# hydrogen_sensors_board_v4_0.net
KiCad netlist of a schematic drawn in EAGLE
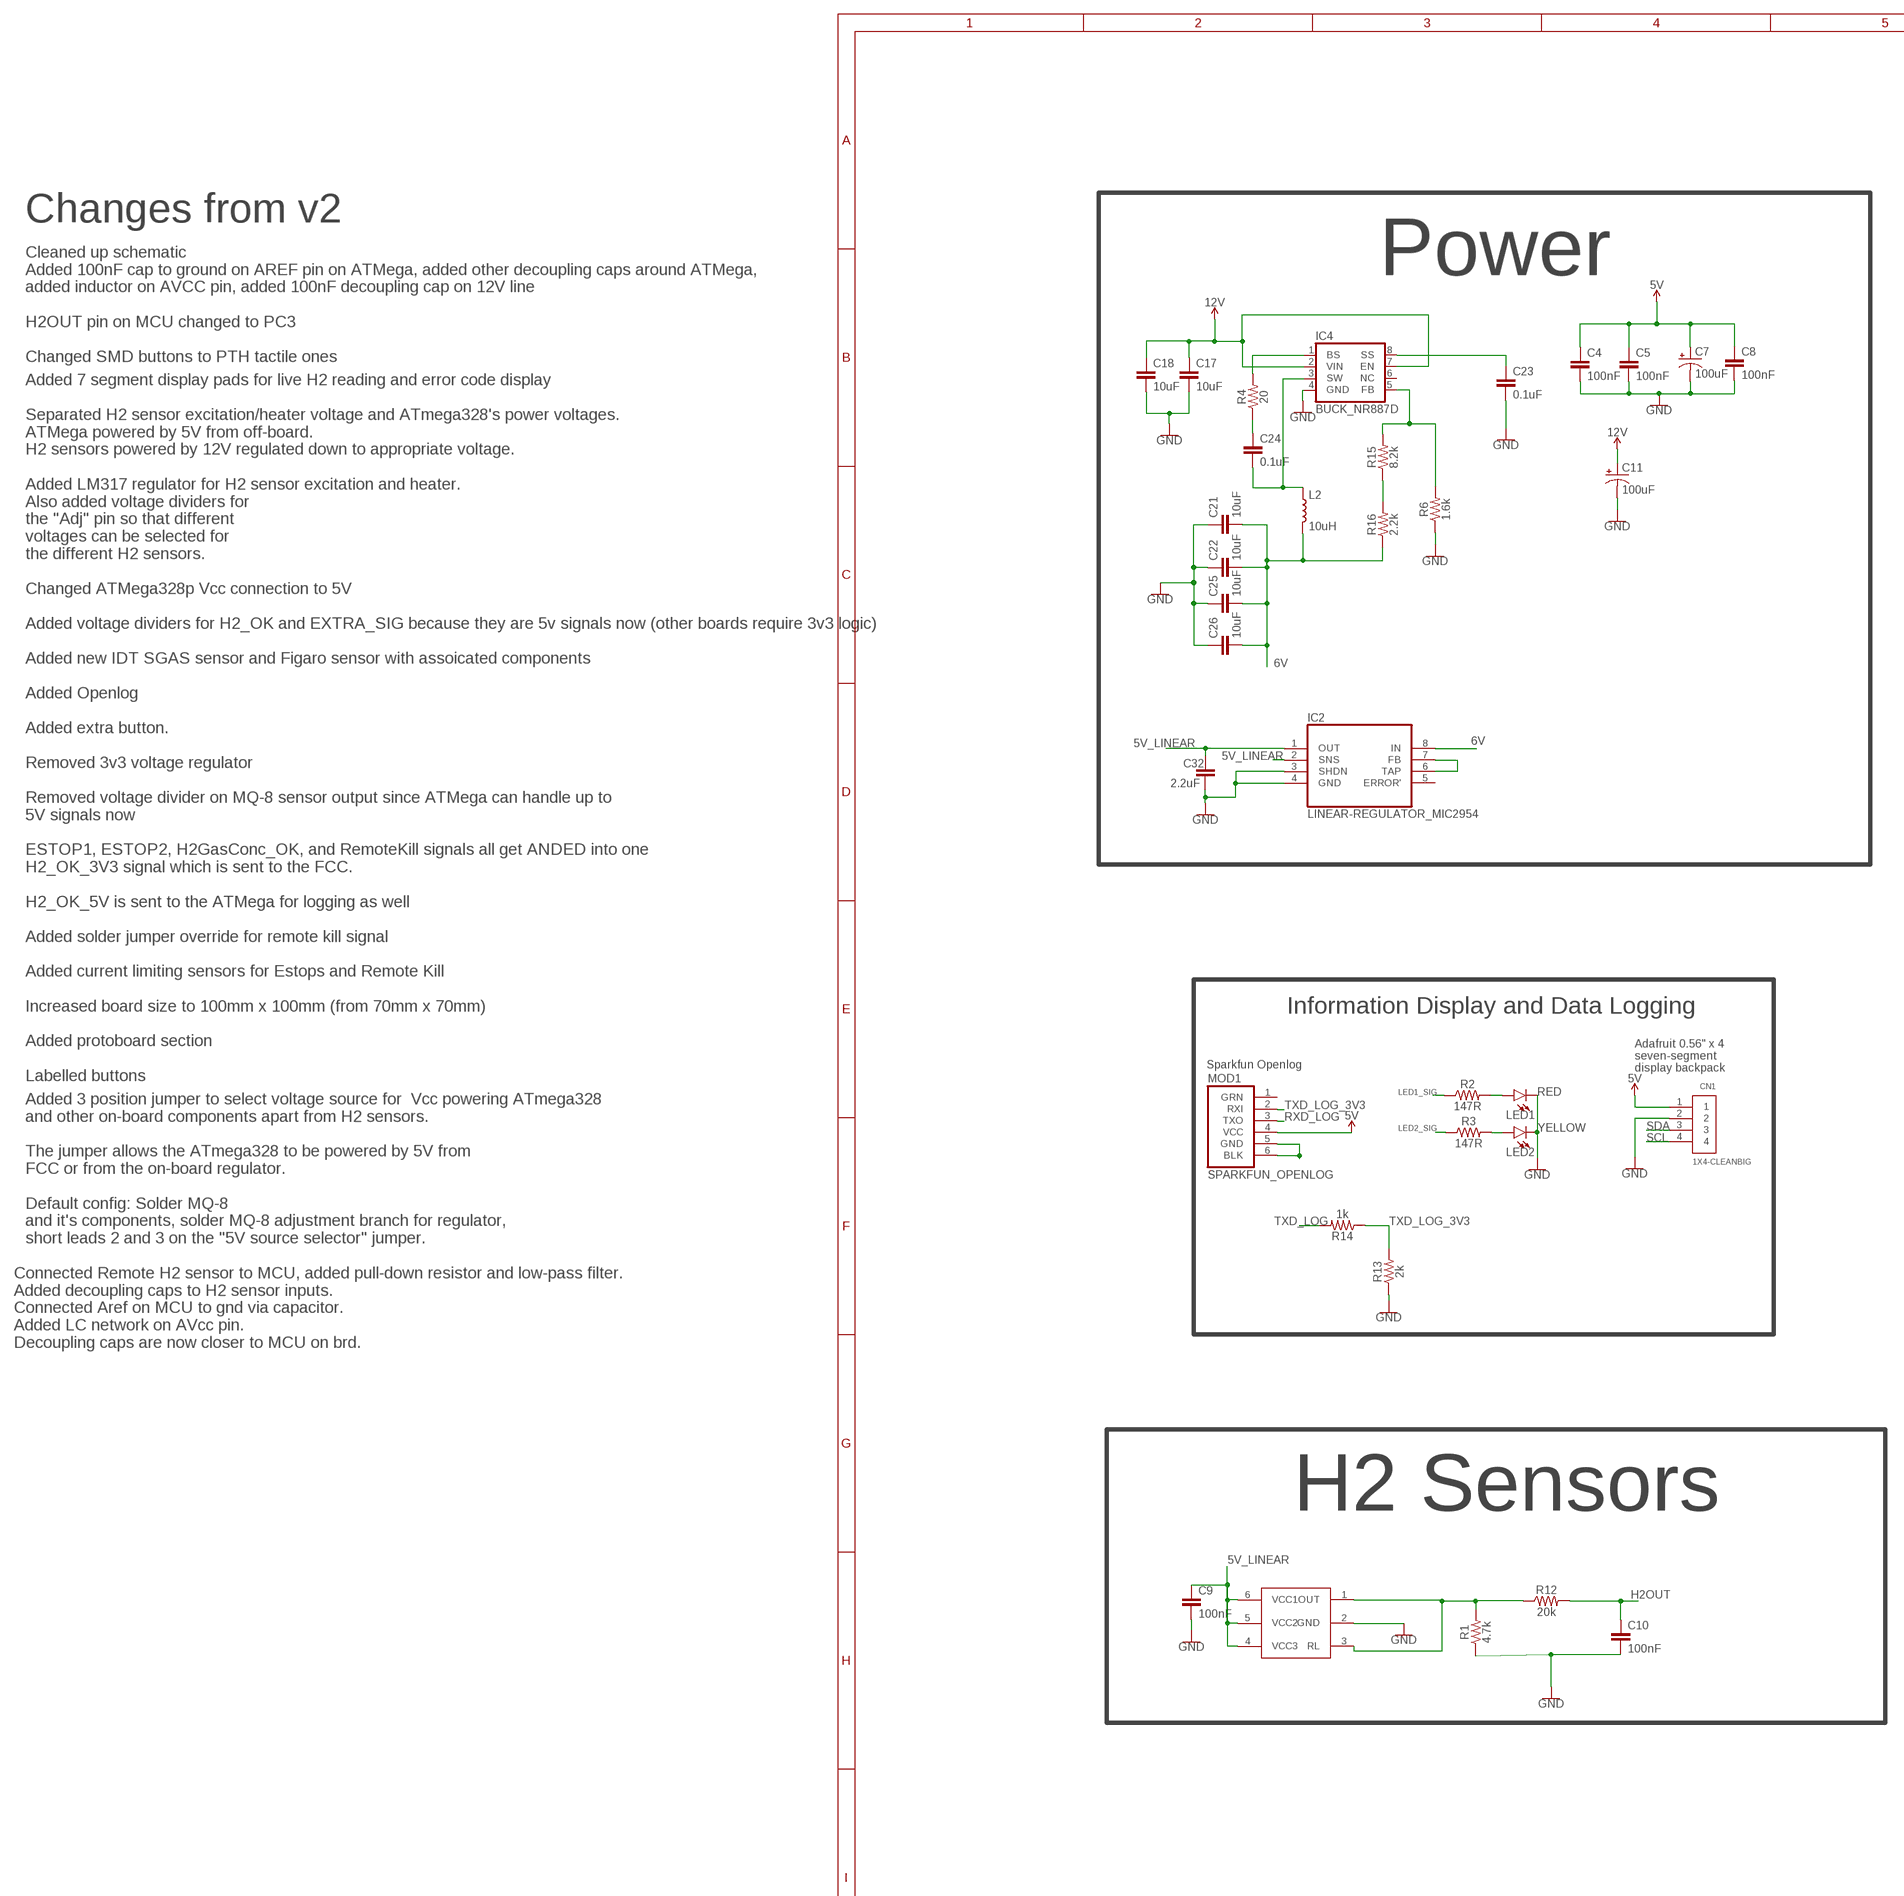
[diagram p0: schematic, sheet 1, part 1 of 2]
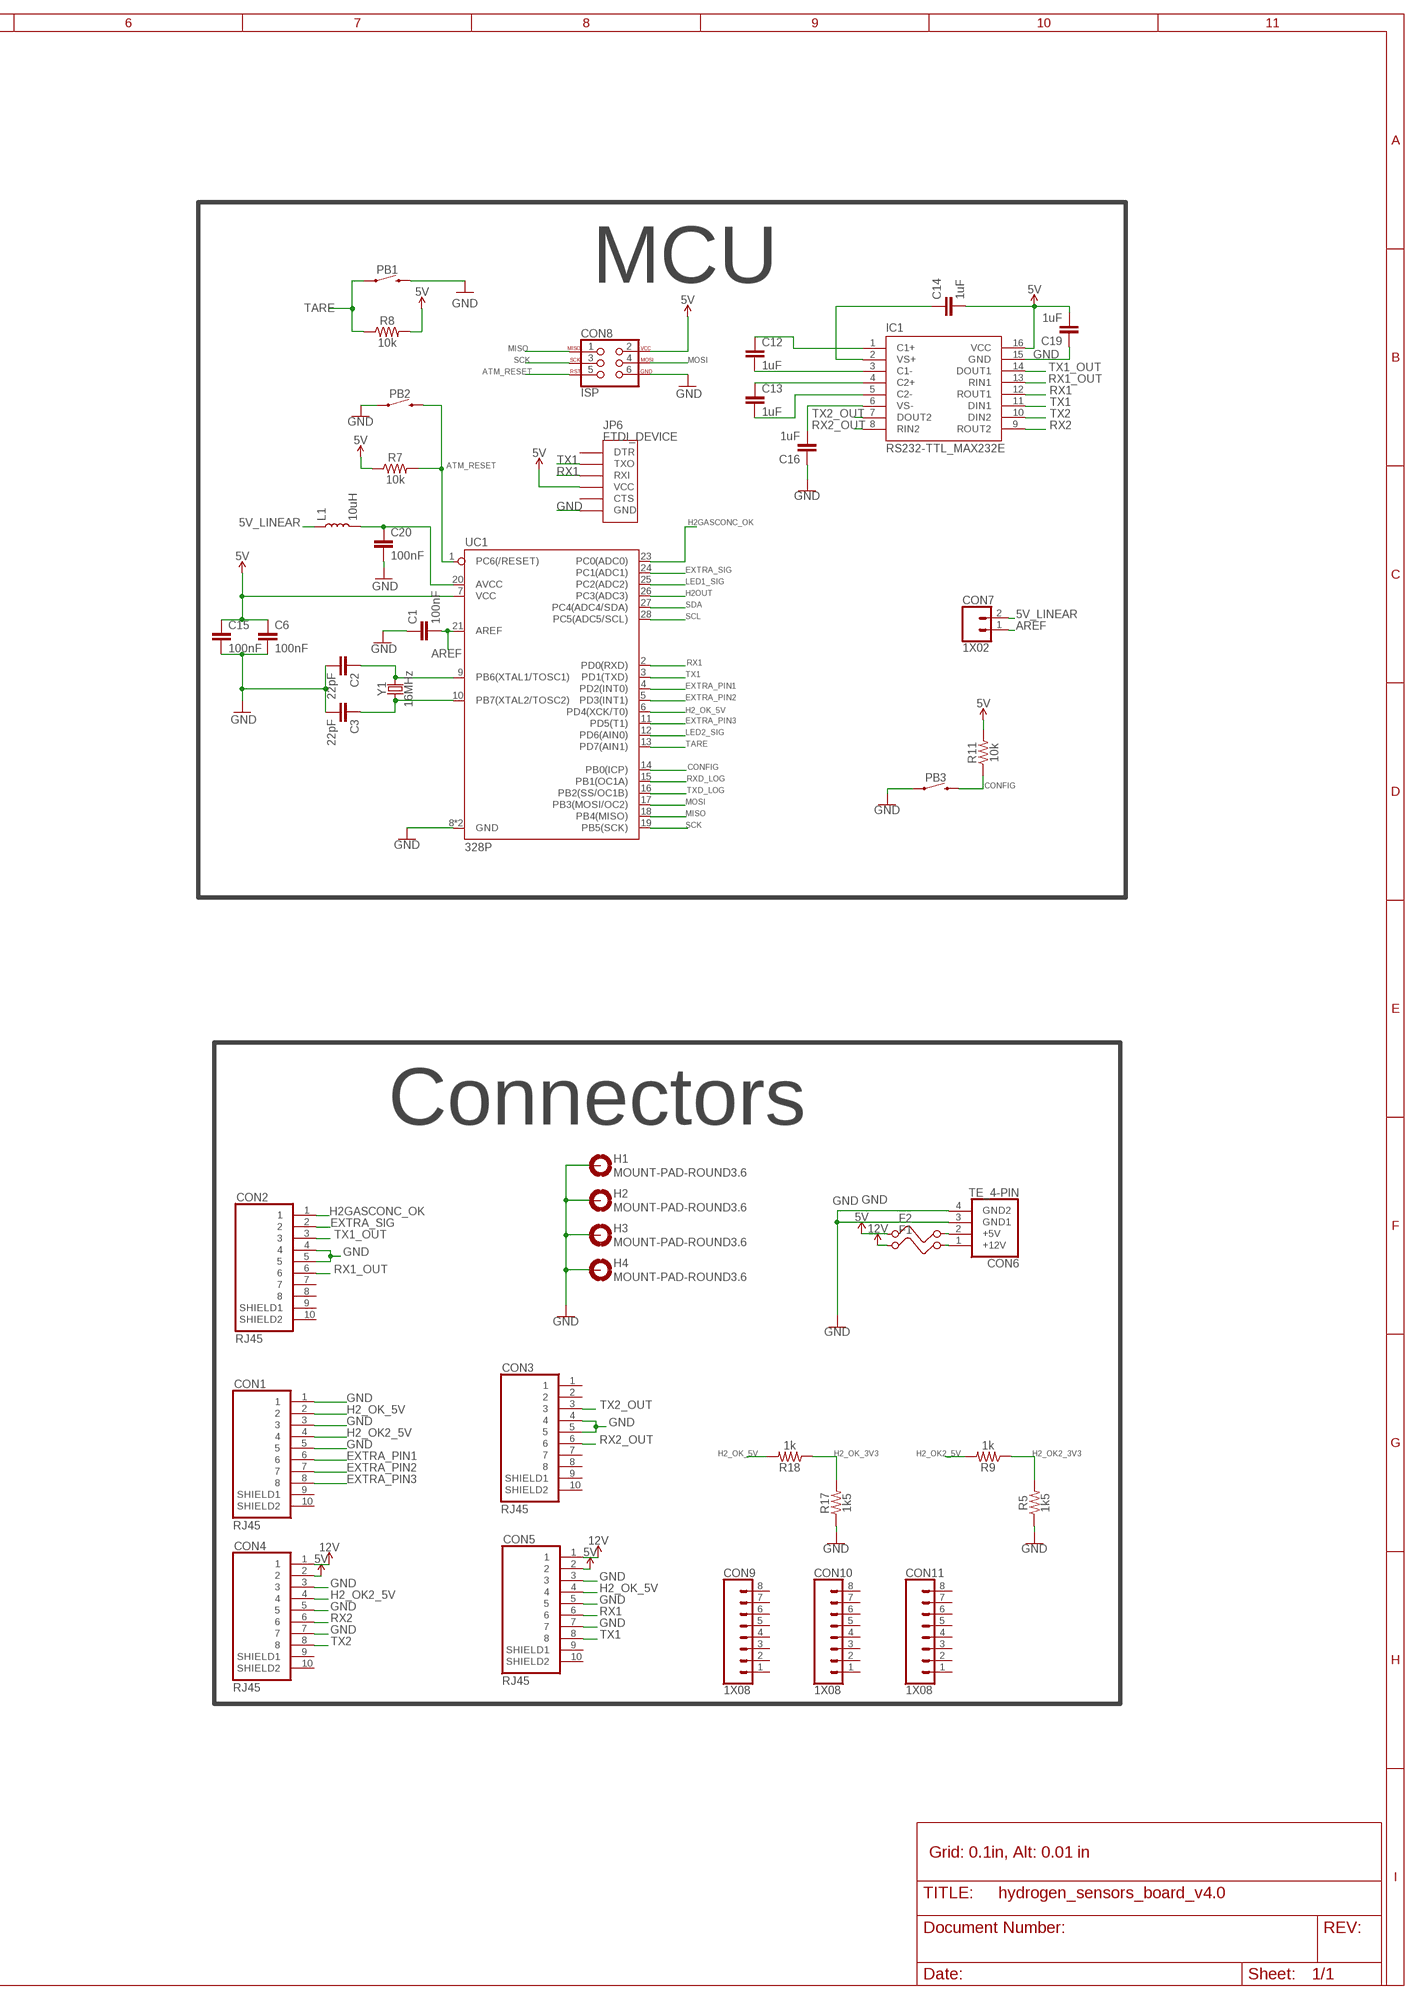
[diagram p1: schematic, sheet 1, part 2 of 2]

(export (version "E")
  (design (tool "Eeschema 10.0.6"))
  (components
    (comp (ref "C1")
      (value "100nF")
      (footprint "eagle-import:0805")
      (libsource (lib "eagle-import") (part "CAPACITOR_0805"))
    )
    (comp (ref "C2")
      (value "22pF")
      (footprint "eagle-import:0805")
      (libsource (lib "eagle-import") (part "CAPACITOR_0805"))
    )
    (comp (ref "C3")
      (value "22pF")
      (footprint "eagle-import:0805")
      (libsource (lib "eagle-import") (part "CAPACITOR_0805"))
    )
    (comp (ref "C4")
      (value "100nF")
      (footprint "eagle-import:0805")
      (libsource (lib "eagle-import") (part "CAPACITOR_0805"))
    )
    (comp (ref "C5")
      (value "100nF")
      (footprint "eagle-import:0805")
      (libsource (lib "eagle-import") (part "CAPACITOR_0805"))
    )
    (comp (ref "C6")
      (value "100nF")
      (footprint "eagle-import:0805")
      (libsource (lib "eagle-import") (part "CAPACITOR_0805"))
    )
    (comp (ref "C7")
      (value "100uF")
      (footprint "eagle-import:CAPACITOR_100UF_50V")
      (libsource (lib "eagle-import") (part "CAPACITOR_ELECTROLYTIC_100UF"))
    )
    (comp (ref "C8")
      (value "100nF")
      (footprint "eagle-import:0805")
      (libsource (lib "eagle-import") (part "CAPACITOR_0805"))
    )
    (comp (ref "C9")
      (value "100nF")
      (footprint "eagle-import:0805")
      (libsource (lib "eagle-import") (part "CAPACITOR_0805"))
    )
    (comp (ref "C10")
      (value "100nF")
      (footprint "eagle-import:0805")
      (libsource (lib "eagle-import") (part "CAPACITOR_0805"))
    )
    (comp (ref "C11")
      (value "100uF")
      (footprint "eagle-import:CAPACITOR_100UF_50V")
      (libsource (lib "eagle-import") (part "CAPACITOR_ELECTROLYTIC_100UF"))
    )
    (comp (ref "C12")
      (value "1uF")
      (footprint "eagle-import:0805")
      (libsource (lib "eagle-import") (part "CAPACITOR_0805"))
    )
    (comp (ref "C13")
      (value "1uF")
      (footprint "eagle-import:0805")
      (libsource (lib "eagle-import") (part "CAPACITOR_0805"))
    )
    (comp (ref "C14")
      (value "1uF")
      (footprint "eagle-import:0805")
      (libsource (lib "eagle-import") (part "CAPACITOR_0805"))
    )
    (comp (ref "C15")
      (value "100nF")
      (footprint "eagle-import:0805")
      (libsource (lib "eagle-import") (part "CAPACITOR_0805"))
    )
    (comp (ref "C16")
      (value "1uF")
      (footprint "eagle-import:0805")
      (libsource (lib "eagle-import") (part "CAPACITOR_0805"))
    )
    (comp (ref "C17")
      (value "10uF")
      (footprint "eagle-import:0805")
      (libsource (lib "eagle-import") (part "CAPACITOR_0805"))
    )
    (comp (ref "C18")
      (value "10uF")
      (footprint "eagle-import:0805")
      (libsource (lib "eagle-import") (part "CAPACITOR_0805"))
    )
    (comp (ref "C19")
      (value "1uF")
      (footprint "eagle-import:0805")
      (libsource (lib "eagle-import") (part "CAPACITOR_0805"))
    )
    (comp (ref "C20")
      (value "100nF")
      (footprint "eagle-import:0805")
      (libsource (lib "eagle-import") (part "CAPACITOR_0805"))
    )
    (comp (ref "C21")
      (value "10uF")
      (footprint "eagle-import:1210")
      (libsource (lib "eagle-import") (part "CAPACITOR_1210"))
    )
    (comp (ref "C22")
      (value "10uF")
      (footprint "eagle-import:1210")
      (libsource (lib "eagle-import") (part "CAPACITOR_1210"))
    )
    (comp (ref "C23")
      (value "0.1uF")
      (footprint "eagle-import:0805")
      (libsource (lib "eagle-import") (part "CAPACITOR_0805"))
    )
    (comp (ref "C24")
      (value "0.1uF")
      (footprint "eagle-import:0805")
      (libsource (lib "eagle-import") (part "CAPACITOR_0805"))
    )
    (comp (ref "C25")
      (value "10uF")
      (footprint "eagle-import:1210")
      (libsource (lib "eagle-import") (part "CAPACITOR_1210"))
    )
    (comp (ref "C26")
      (value "10uF")
      (footprint "eagle-import:1210")
      (libsource (lib "eagle-import") (part "CAPACITOR_1210"))
    )
    (comp (ref "C32")
      (value "2.2uF")
      (footprint "eagle-import:0805")
      (libsource (lib "eagle-import") (part "CAPACITOR_0805"))
    )
    (comp (ref "CN1")
      (value "1X4-CLEANBIG")
      (footprint "eagle-import:1X04-CLEANBIG")
      (libsource (lib "eagle-import") (part "1X4-CLEANBIG"))
    )
    (comp (ref "CON1")
      (value "RJ45")
      (footprint "eagle-import:RJ45")
      (libsource (lib "eagle-import") (part "RJ45"))
    )
    (comp (ref "CON2")
      (value "RJ45")
      (footprint "eagle-import:RJ45")
      (libsource (lib "eagle-import") (part "RJ45"))
    )
    (comp (ref "CON3")
      (value "RJ45")
      (footprint "eagle-import:RJ45")
      (libsource (lib "eagle-import") (part "RJ45"))
    )
    (comp (ref "CON4")
      (value "RJ45")
      (footprint "eagle-import:RJ45")
      (libsource (lib "eagle-import") (part "RJ45"))
    )
    (comp (ref "CON5")
      (value "RJ45")
      (footprint "eagle-import:RJ45")
      (libsource (lib "eagle-import") (part "RJ45"))
    )
    (comp (ref "CON6")
      (value "TE_4-PIN")
      (footprint "eagle-import:TE_4-PIN")
      (libsource (lib "eagle-import") (part "TE_4-PIN"))
    )
    (comp (ref "CON7")
      (value "1X02")
      (footprint "eagle-import:1X02")
      (libsource (lib "eagle-import") (part "1X02"))
    )
    (comp (ref "CON8")
      (value "ISP")
      (footprint "eagle-import:ISP_CONNECTOR")
      (libsource (lib "eagle-import") (part "ISP"))
    )
    (comp (ref "CON9")
      (value "1X08")
      (footprint "eagle-import:1X08")
      (libsource (lib "eagle-import") (part "1X08"))
    )
    (comp (ref "CON10")
      (value "1X08")
      (footprint "eagle-import:1X08")
      (libsource (lib "eagle-import") (part "1X08"))
    )
    (comp (ref "CON11")
      (value "1X08")
      (footprint "eagle-import:1X08")
      (libsource (lib "eagle-import") (part "1X08"))
    )
    (comp (ref "F1")
      (value "FUSE_1210")
      (footprint "eagle-import:1210")
      (libsource (lib "eagle-import") (part "FUSE_1210"))
    )
    (comp (ref "F2")
      (value "FUSE_1210")
      (footprint "eagle-import:1210")
      (libsource (lib "eagle-import") (part "FUSE_1210"))
    )
    (comp (ref "H1")
      (value "MOUNT-PAD-ROUND3.6")
      (footprint "eagle-import:3,6-PAD")
      (libsource (lib "eagle-import") (part "MOUNT-PAD-ROUND3.6"))
    )
    (comp (ref "H2")
      (value "MOUNT-PAD-ROUND3.6")
      (footprint "eagle-import:3,6-PAD")
      (libsource (lib "eagle-import") (part "MOUNT-PAD-ROUND3.6"))
    )
    (comp (ref "H3")
      (value "MOUNT-PAD-ROUND3.6")
      (footprint "eagle-import:3,6-PAD")
      (libsource (lib "eagle-import") (part "MOUNT-PAD-ROUND3.6"))
    )
    (comp (ref "H4")
      (value "MOUNT-PAD-ROUND3.6")
      (footprint "eagle-import:3,6-PAD")
      (libsource (lib "eagle-import") (part "MOUNT-PAD-ROUND3.6"))
    )
    (comp (ref "IC1")
      (value "RS232-TTL_MAX232E")
      (footprint "eagle-import:DIP16")
      (libsource (lib "eagle-import") (part "RS232-TTL_MAX232E"))
    )
    (comp (ref "IC2")
      (value "LINEAR-REGULATOR_MIC2954")
      (footprint "eagle-import:SOIC8")
      (libsource (lib "eagle-import") (part "LINEAR-REGULATOR_MIC2954"))
    )
    (comp (ref "IC4")
      (value "BUCK_NR887D")
      (footprint "eagle-import:DIP08")
      (libsource (lib "eagle-import") (part "BUCK_NR887D"))
    )
    (comp (ref "JP6")
      (value "FTDI_DEVICE")
      (footprint "eagle-import:FTDI_DEVICE_SIDE")
      (libsource (lib "eagle-import") (part "FTDI_DEVICE"))
    )
    (comp (ref "L1")
      (value "10uH")
      (footprint "eagle-import:0805")
      (libsource (lib "eagle-import") (part "INDUCTOR_0805"))
    )
    (comp (ref "L2")
      (value "10uH")
      (footprint "eagle-import:INDUCTOR_MURATA_DEM8030C")
      (libsource (lib "eagle-import") (part "INDUCTOR_MURATA_DEM8030C"))
    )
    (comp (ref "LED1")
      (value "RED")
      (footprint "eagle-import:0805_LED")
      (libsource (lib "eagle-import") (part "LED_0805"))
    )
    (comp (ref "LED2")
      (value "YELLOW")
      (footprint "eagle-import:0805_LED")
      (libsource (lib "eagle-import") (part "LED_0805"))
    )
    (comp (ref "MOD1")
      (value "SPARKFUN_OPENLOG")
      (footprint "eagle-import:SPARKFUN_OPENLOG")
      (libsource (lib "eagle-import") (part "SPARKFUN_OPENLOG"))
    )
    (comp (ref "PB1")
      (value "PUSHBUTTON")
      (footprint "eagle-import:PUSHBUTTON")
      (libsource (lib "eagle-import") (part "PUSHBUTTON"))
    )
    (comp (ref "PB2")
      (value "PUSHBUTTON")
      (footprint "eagle-import:PUSHBUTTON")
      (libsource (lib "eagle-import") (part "PUSHBUTTON"))
    )
    (comp (ref "PB3")
      (value "PUSHBUTTON")
      (footprint "eagle-import:PUSHBUTTON")
      (libsource (lib "eagle-import") (part "PUSHBUTTON"))
    )
    (comp (ref "R1")
      (value "4.7k")
      (footprint "eagle-import:0805")
      (libsource (lib "eagle-import") (part "RESISTOR_0805"))
    )
    (comp (ref "R2")
      (value "147R")
      (footprint "eagle-import:0805")
      (libsource (lib "eagle-import") (part "RESISTOR_0805"))
    )
    (comp (ref "R3")
      (value "147R")
      (footprint "eagle-import:0805")
      (libsource (lib "eagle-import") (part "RESISTOR_0805"))
    )
    (comp (ref "R4")
      (value "20")
      (footprint "eagle-import:0805")
      (libsource (lib "eagle-import") (part "RESISTOR_0805"))
    )
    (comp (ref "R5")
      (value "1k5")
      (footprint "eagle-import:0805")
      (libsource (lib "eagle-import") (part "RESISTOR_0805"))
    )
    (comp (ref "R6")
      (value "1.6k")
      (footprint "eagle-import:0805")
      (libsource (lib "eagle-import") (part "RESISTOR_0805"))
    )
    (comp (ref "R7")
      (value "10k")
      (footprint "eagle-import:0805")
      (libsource (lib "eagle-import") (part "RESISTOR_0805"))
    )
    (comp (ref "R8")
      (value "10k")
      (footprint "eagle-import:0805")
      (libsource (lib "eagle-import") (part "RESISTOR_0805"))
    )
    (comp (ref "R9")
      (value "1k")
      (footprint "eagle-import:0805")
      (libsource (lib "eagle-import") (part "RESISTOR_0805"))
    )
    (comp (ref "R11")
      (value "10k")
      (footprint "eagle-import:0805")
      (libsource (lib "eagle-import") (part "RESISTOR_0805"))
    )
    (comp (ref "R12")
      (value "20k")
      (footprint "eagle-import:0805")
      (libsource (lib "eagle-import") (part "RESISTOR_0805"))
    )
    (comp (ref "R13")
      (value "2k")
      (footprint "eagle-import:0805")
      (libsource (lib "eagle-import") (part "RESISTOR_0805"))
    )
    (comp (ref "R14")
      (value "1k")
      (footprint "eagle-import:0805")
      (libsource (lib "eagle-import") (part "RESISTOR_0805"))
    )
    (comp (ref "R15")
      (value "8.2k")
      (footprint "eagle-import:0805")
      (libsource (lib "eagle-import") (part "RESISTOR_0805"))
    )
    (comp (ref "R16")
      (value "2.2k")
      (footprint "eagle-import:0805")
      (libsource (lib "eagle-import") (part "RESISTOR_0805"))
    )
    (comp (ref "R17")
      (value "1k5")
      (footprint "eagle-import:0805")
      (libsource (lib "eagle-import") (part "RESISTOR_0805"))
    )
    (comp (ref "R18")
      (value "1k")
      (footprint "eagle-import:0805")
      (libsource (lib "eagle-import") (part "RESISTOR_0805"))
    )
    (comp (ref "U$1")
      (value "MQ-8MQ-8")
      (footprint "eagle-import:MQ-8")
      (libsource (lib "eagle-import") (part "MQ-8MQ-8"))
    )
    (comp (ref "UC1")
      (value "328P")
      (footprint "eagle-import:DIP28")
      (libsource (lib "eagle-import") (part "ATMEGA328P_DIP28"))
    )
    (comp (ref "Y1")
      (value "16MHz")
      (footprint "eagle-import:HC49US")
      (libsource (lib "eagle-import") (part "CRYSTAL-16MHZPTH-HC49US"))
    )
  )
  (nets
    (net (code "1") (name "/5V_LINEAR") (class "Default")
      (node (ref "C32") (pin "1") (pinfunction "1_1") (pintype "passive"))
      (node (ref "C9") (pin "1") (pinfunction "1_1") (pintype "passive"))
      (node (ref "CON7") (pin "2") (pinfunction "2_2") (pintype "passive"))
      (node (ref "IC2") (pin "1") (pinfunction "OUT_1") (pintype "bidirectional"))
      (node (ref "IC2") (pin "2") (pinfunction "SNS_2") (pintype "bidirectional"))
      (node (ref "L1") (pin "1") (pinfunction "1_1") (pintype "passive"))
      (node (ref "U$1") (pin "4") (pinfunction "VCC3_4") (pintype "bidirectional"))
      (node (ref "U$1") (pin "5") (pinfunction "VCC2_5") (pintype "bidirectional"))
      (node (ref "U$1") (pin "6") (pinfunction "VCC1_6") (pintype "bidirectional"))
    )
    (net (code "2") (name "/6V") (class "Default")
      (node (ref "C21") (pin "2") (pinfunction "2_2") (pintype "passive"))
      (node (ref "C22") (pin "2") (pinfunction "2_2") (pintype "passive"))
      (node (ref "C25") (pin "2") (pinfunction "2_2") (pintype "passive"))
      (node (ref "C26") (pin "2") (pinfunction "2_2") (pintype "passive"))
      (node (ref "IC2") (pin "8") (pinfunction "IN_8") (pintype "bidirectional"))
      (node (ref "L2") (pin "P$2") (pinfunction "2_P$2") (pintype "passive"))
      (node (ref "R16") (pin "1") (pinfunction "1_1") (pintype "passive"))
    )
    (net (code "3") (name "/AREF") (class "Default")
      (node (ref "C1") (pin "2") (pinfunction "2_2") (pintype "passive"))
      (node (ref "CON7") (pin "1") (pinfunction "1_1") (pintype "passive"))
      (node (ref "UC1") (pin "21") (pinfunction "AREF_21") (pintype "bidirectional"))
    )
    (net (code "4") (name "/ATM_RESET") (class "Default")
      (node (ref "CON8") (pin "5") (pinfunction "5_5") (pintype "passive"))
      (node (ref "PB2") (pin "3") (pinfunction "2_3") (pintype "passive"))
      (node (ref "PB2") (pin "4") (pinfunction "2_4") (pintype "passive"))
      (node (ref "R7") (pin "2") (pinfunction "2_2") (pintype "passive"))
      (node (ref "UC1") (pin "1") (pinfunction "PC6(/RESET)_1") (pintype "bidirectional"))
    )
    (net (code "5") (name "/CONFIG") (class "Default")
      (node (ref "PB3") (pin "3") (pinfunction "2_3") (pintype "passive"))
      (node (ref "PB3") (pin "4") (pinfunction "2_4") (pintype "passive"))
      (node (ref "R11") (pin "1") (pinfunction "1_1") (pintype "passive"))
      (node (ref "UC1") (pin "14") (pinfunction "PB0(ICP)_14") (pintype "bidirectional"))
    )
    (net (code "6") (name "/EXTRA_PIN1") (class "Default")
      (node (ref "CON1") (pin "6") (pinfunction "6_6") (pintype "passive"))
      (node (ref "UC1") (pin "4") (pinfunction "PD2(INT0)_4") (pintype "bidirectional"))
    )
    (net (code "7") (name "/EXTRA_PIN2") (class "Default")
      (node (ref "CON1") (pin "7") (pinfunction "7_7") (pintype "passive"))
      (node (ref "UC1") (pin "5") (pinfunction "PD3(INT1)_5") (pintype "bidirectional"))
    )
    (net (code "8") (name "/EXTRA_PIN3") (class "Default")
      (node (ref "CON1") (pin "8") (pinfunction "8_8") (pintype "passive"))
      (node (ref "UC1") (pin "11") (pinfunction "PD5(T1)_11") (pintype "bidirectional"))
    )
    (net (code "9") (name "/EXTRA_SIG") (class "Default")
      (node (ref "CON2") (pin "2") (pinfunction "2_2") (pintype "passive"))
      (node (ref "UC1") (pin "24") (pinfunction "PC1(ADC1)_24") (pintype "bidirectional"))
    )
    (net (code "10") (name "/H2GASCONC_OK") (class "Default")
      (node (ref "CON2") (pin "1") (pinfunction "1_1") (pintype "passive"))
      (node (ref "UC1") (pin "23") (pinfunction "PC0(ADC0)_23") (pintype "bidirectional"))
    )
    (net (code "11") (name "/H2OUT") (class "Default")
      (node (ref "C10") (pin "1") (pinfunction "1_1") (pintype "passive"))
      (node (ref "R12") (pin "2") (pinfunction "2_2") (pintype "passive"))
      (node (ref "UC1") (pin "26") (pinfunction "PC3(ADC3)_26") (pintype "bidirectional"))
    )
    (net (code "12") (name "/H2_OK2_3V3") (class "Default")
      (node (ref "R5") (pin "2") (pinfunction "2_2") (pintype "passive"))
      (node (ref "R9") (pin "1") (pinfunction "1_1") (pintype "passive"))
    )
    (net (code "13") (name "/H2_OK2_5V") (class "Default")
      (node (ref "CON1") (pin "4") (pinfunction "4_4") (pintype "passive"))
      (node (ref "CON4") (pin "4") (pinfunction "4_4") (pintype "passive"))
      (node (ref "R9") (pin "2") (pinfunction "2_2") (pintype "passive"))
    )
    (net (code "14") (name "/H2_OK_3V3") (class "Default")
      (node (ref "R17") (pin "2") (pinfunction "2_2") (pintype "passive"))
      (node (ref "R18") (pin "1") (pinfunction "1_1") (pintype "passive"))
    )
    (net (code "15") (name "/H2_OK_5V") (class "Default")
      (node (ref "CON1") (pin "2") (pinfunction "2_2") (pintype "passive"))
      (node (ref "CON5") (pin "4") (pinfunction "4_4") (pintype "passive"))
      (node (ref "R18") (pin "2") (pinfunction "2_2") (pintype "passive"))
      (node (ref "UC1") (pin "6") (pinfunction "PD4(XCK/T0)_6") (pintype "bidirectional"))
    )
    (net (code "16") (name "/LED1_SIG") (class "Default")
      (node (ref "R2") (pin "1") (pinfunction "1_1") (pintype "passive"))
      (node (ref "UC1") (pin "25") (pinfunction "PC2(ADC2)_25") (pintype "bidirectional"))
    )
    (net (code "17") (name "/LED2_SIG") (class "Default")
      (node (ref "R3") (pin "1") (pinfunction "1_1") (pintype "passive"))
      (node (ref "UC1") (pin "12") (pinfunction "PD6(AIN0)_12") (pintype "bidirectional"))
    )
    (net (code "18") (name "/MISO") (class "Default")
      (node (ref "CON8") (pin "1") (pinfunction "1_1") (pintype "passive"))
      (node (ref "UC1") (pin "18") (pinfunction "PB4(MISO)_18") (pintype "bidirectional"))
    )
    (net (code "19") (name "/MOSI") (class "Default")
      (node (ref "CON8") (pin "4") (pinfunction "4_4") (pintype "passive"))
      (node (ref "UC1") (pin "17") (pinfunction "PB3(MOSI/OC2)_17") (pintype "bidirectional"))
    )
    (net (code "20") (name "/RX1") (class "Default")
      (node (ref "CON5") (pin "6") (pinfunction "6_6") (pintype "passive"))
      (node (ref "IC1") (pin "12") (pinfunction "ROUT1_12") (pintype "bidirectional"))
      (node (ref "JP6") (pin "P$3") (pinfunction "RXI_P$3") (pintype "bidirectional"))
      (node (ref "UC1") (pin "2") (pinfunction "PD0(RXD)_2") (pintype "bidirectional"))
    )
    (net (code "21") (name "/RX1_OUT") (class "Default")
      (node (ref "CON2") (pin "6") (pinfunction "6_6") (pintype "passive"))
      (node (ref "IC1") (pin "13") (pinfunction "RIN1_13") (pintype "bidirectional"))
    )
    (net (code "22") (name "/RX2") (class "Default")
      (node (ref "CON4") (pin "6") (pinfunction "6_6") (pintype "passive"))
      (node (ref "IC1") (pin "9") (pinfunction "ROUT2_9") (pintype "bidirectional"))
    )
    (net (code "23") (name "/RX2_OUT") (class "Default")
      (node (ref "CON3") (pin "6") (pinfunction "6_6") (pintype "passive"))
      (node (ref "IC1") (pin "8") (pinfunction "RIN2_8") (pintype "bidirectional"))
    )
    (net (code "24") (name "/RXD_LOG") (class "Default")
      (node (ref "MOD1") (pin "3") (pinfunction "TXO_3") (pintype "passive"))
      (node (ref "UC1") (pin "15") (pinfunction "PB1(OC1A)_15") (pintype "bidirectional"))
    )
    (net (code "25") (name "/SCK") (class "Default")
      (node (ref "CON8") (pin "3") (pinfunction "3_3") (pintype "passive"))
      (node (ref "UC1") (pin "19") (pinfunction "PB5(SCK)_19") (pintype "bidirectional"))
    )
    (net (code "26") (name "/SCL") (class "Default")
      (node (ref "CN1") (pin "4") (pinfunction "4_4") (pintype "bidirectional"))
      (node (ref "UC1") (pin "28") (pinfunction "PC5(ADC5/SCL)_28") (pintype "bidirectional"))
    )
    (net (code "27") (name "/SDA") (class "Default")
      (node (ref "CN1") (pin "3") (pinfunction "3_3") (pintype "bidirectional"))
      (node (ref "UC1") (pin "27") (pinfunction "PC4(ADC4/SDA)_27") (pintype "bidirectional"))
    )
    (net (code "28") (name "/TARE") (class "Default")
      (node (ref "PB1") (pin "1") (pinfunction "1_1") (pintype "passive"))
      (node (ref "PB1") (pin "2") (pinfunction "1_2") (pintype "passive"))
      (node (ref "R8") (pin "1") (pinfunction "1_1") (pintype "passive"))
      (node (ref "UC1") (pin "13") (pinfunction "PD7(AIN1)_13") (pintype "bidirectional"))
    )
    (net (code "29") (name "/TX1") (class "Default")
      (node (ref "CON5") (pin "8") (pinfunction "8_8") (pintype "passive"))
      (node (ref "IC1") (pin "11") (pinfunction "DIN1_11") (pintype "bidirectional"))
      (node (ref "JP6") (pin "P$2") (pinfunction "TXO_P$2") (pintype "bidirectional"))
      (node (ref "UC1") (pin "3") (pinfunction "PD1(TXD)_3") (pintype "bidirectional"))
    )
    (net (code "30") (name "/TX1_OUT") (class "Default")
      (node (ref "CON2") (pin "3") (pinfunction "3_3") (pintype "passive"))
      (node (ref "IC1") (pin "14") (pinfunction "DOUT1_14") (pintype "bidirectional"))
    )
    (net (code "31") (name "/TX2") (class "Default")
      (node (ref "CON4") (pin "8") (pinfunction "8_8") (pintype "passive"))
      (node (ref "IC1") (pin "10") (pinfunction "DIN2_10") (pintype "bidirectional"))
    )
    (net (code "32") (name "/TX2_OUT") (class "Default")
      (node (ref "CON3") (pin "3") (pinfunction "3_3") (pintype "passive"))
      (node (ref "IC1") (pin "7") (pinfunction "DOUT2_7") (pintype "bidirectional"))
    )
    (net (code "33") (name "/TXD_LOG") (class "Default")
      (node (ref "R14") (pin "2") (pinfunction "2_2") (pintype "passive"))
      (node (ref "UC1") (pin "16") (pinfunction "PB2(SS/OC1B)_16") (pintype "bidirectional"))
    )
    (net (code "34") (name "/TXD_LOG_3V3") (class "Default")
      (node (ref "MOD1") (pin "2") (pinfunction "RXI_2") (pintype "passive"))
      (node (ref "R13") (pin "2") (pinfunction "2_2") (pintype "passive"))
      (node (ref "R14") (pin "1") (pinfunction "1_1") (pintype "passive"))
    )
    (net (code "35") (name "5V") (class "Default")
      (node (ref "C14") (pin "2") (pinfunction "2_2") (pintype "passive"))
      (node (ref "C15") (pin "1") (pinfunction "1_1") (pintype "passive"))
      (node (ref "C19") (pin "2") (pinfunction "2_2") (pintype "passive"))
      (node (ref "C4") (pin "1") (pinfunction "1_1") (pintype "passive"))
      (node (ref "C5") (pin "1") (pinfunction "1_1") (pintype "passive"))
      (node (ref "C6") (pin "1") (pinfunction "1_1") (pintype "passive"))
      (node (ref "C7") (pin "+") (pinfunction "+_+") (pintype "passive"))
      (node (ref "C8") (pin "1") (pinfunction "1_1") (pintype "passive"))
      (node (ref "CN1") (pin "1") (pinfunction "1_1") (pintype "bidirectional"))
      (node (ref "CON4") (pin "2") (pinfunction "2_2") (pintype "passive"))
      (node (ref "CON5") (pin "2") (pinfunction "2_2") (pintype "passive"))
      (node (ref "CON8") (pin "2") (pinfunction "2_2") (pintype "passive"))
      (node (ref "F2") (pin "1") (pinfunction "1_1") (pintype "passive"))
      (node (ref "IC1") (pin "16") (pinfunction "VCC_16") (pintype "bidirectional"))
      (node (ref "JP6") (pin "P$4") (pinfunction "VCC_P$4") (pintype "bidirectional"))
      (node (ref "MOD1") (pin "4") (pinfunction "VCC_4") (pintype "passive"))
      (node (ref "R11") (pin "2") (pinfunction "2_2") (pintype "passive"))
      (node (ref "R7") (pin "1") (pinfunction "1_1") (pintype "passive"))
      (node (ref "R8") (pin "2") (pinfunction "2_2") (pintype "passive"))
      (node (ref "UC1") (pin "7") (pinfunction "VCC_7") (pintype "bidirectional"))
    )
    (net (code "36") (name "12V") (class "Default")
      (node (ref "C11") (pin "+") (pinfunction "+_+") (pintype "passive"))
      (node (ref "C17") (pin "1") (pinfunction "1_1") (pintype "passive"))
      (node (ref "C18") (pin "1") (pinfunction "1_1") (pintype "passive"))
      (node (ref "CON4") (pin "1") (pinfunction "1_1") (pintype "passive"))
      (node (ref "CON5") (pin "1") (pinfunction "1_1") (pintype "passive"))
      (node (ref "F1") (pin "1") (pinfunction "1_1") (pintype "passive"))
      (node (ref "IC4") (pin "2") (pinfunction "VIN_2") (pintype "bidirectional"))
      (node (ref "IC4") (pin "7") (pinfunction "EN_7") (pintype "bidirectional"))
    )
    (net (code "37") (name "GND") (class "Default")
      (node (ref "C1") (pin "1") (pinfunction "1_1") (pintype "passive"))
      (node (ref "C10") (pin "2") (pinfunction "2_2") (pintype "passive"))
      (node (ref "C11") (pin "-") (pinfunction "-_-") (pintype "passive"))
      (node (ref "C15") (pin "2") (pinfunction "2_2") (pintype "passive"))
      (node (ref "C16") (pin "1") (pinfunction "1_1") (pintype "passive"))
      (node (ref "C17") (pin "2") (pinfunction "2_2") (pintype "passive"))
      (node (ref "C18") (pin "2") (pinfunction "2_2") (pintype "passive"))
      (node (ref "C19") (pin "1") (pinfunction "1_1") (pintype "passive"))
      (node (ref "C2") (pin "2") (pinfunction "2_2") (pintype "passive"))
      (node (ref "C20") (pin "2") (pinfunction "2_2") (pintype "passive"))
      (node (ref "C21") (pin "1") (pinfunction "1_1") (pintype "passive"))
      (node (ref "C22") (pin "1") (pinfunction "1_1") (pintype "passive"))
      (node (ref "C23") (pin "2") (pinfunction "2_2") (pintype "passive"))
      (node (ref "C25") (pin "1") (pinfunction "1_1") (pintype "passive"))
      (node (ref "C26") (pin "1") (pinfunction "1_1") (pintype "passive"))
      (node (ref "C3") (pin "2") (pinfunction "2_2") (pintype "passive"))
      (node (ref "C32") (pin "2") (pinfunction "2_2") (pintype "passive"))
      (node (ref "C4") (pin "2") (pinfunction "2_2") (pintype "passive"))
      (node (ref "C5") (pin "2") (pinfunction "2_2") (pintype "passive"))
      (node (ref "C6") (pin "2") (pinfunction "2_2") (pintype "passive"))
      (node (ref "C7") (pin "-") (pinfunction "-_-") (pintype "passive"))
      (node (ref "C8") (pin "2") (pinfunction "2_2") (pintype "passive"))
      (node (ref "C9") (pin "2") (pinfunction "2_2") (pintype "passive"))
      (node (ref "CN1") (pin "2") (pinfunction "2_2") (pintype "bidirectional"))
      (node (ref "CON1") (pin "1") (pinfunction "1_1") (pintype "passive"))
      (node (ref "CON1") (pin "3") (pinfunction "3_3") (pintype "passive"))
      (node (ref "CON1") (pin "5") (pinfunction "5_5") (pintype "passive"))
      (node (ref "CON2") (pin "4") (pinfunction "4_4") (pintype "passive"))
      (node (ref "CON2") (pin "5") (pinfunction "5_5") (pintype "passive"))
      (node (ref "CON3") (pin "4") (pinfunction "4_4") (pintype "passive"))
      (node (ref "CON3") (pin "5") (pinfunction "5_5") (pintype "passive"))
      (node (ref "CON4") (pin "3") (pinfunction "3_3") (pintype "passive"))
      (node (ref "CON4") (pin "5") (pinfunction "5_5") (pintype "passive"))
      (node (ref "CON4") (pin "7") (pinfunction "7_7") (pintype "passive"))
      (node (ref "CON5") (pin "3") (pinfunction "3_3") (pintype "passive"))
      (node (ref "CON5") (pin "5") (pinfunction "5_5") (pintype "passive"))
      (node (ref "CON5") (pin "7") (pinfunction "7_7") (pintype "passive"))
      (node (ref "CON6") (pin "3") (pinfunction "GND1_3") (pintype "passive"))
      (node (ref "CON6") (pin "4") (pinfunction "GND2_4") (pintype "passive"))
      (node (ref "CON8") (pin "6") (pinfunction "6_6") (pintype "passive"))
      (node (ref "H1") (pin "B3,6") (pinfunction "MOUNT_B3,6") (pintype "passive"))
      (node (ref "H2") (pin "B3,6") (pinfunction "MOUNT_B3,6") (pintype "passive"))
      (node (ref "H3") (pin "B3,6") (pinfunction "MOUNT_B3,6") (pintype "passive"))
      (node (ref "H4") (pin "B3,6") (pinfunction "MOUNT_B3,6") (pintype "passive"))
      (node (ref "IC1") (pin "15") (pinfunction "GND_15") (pintype "bidirectional"))
      (node (ref "IC2") (pin "3") (pinfunction "SHDN_3") (pintype "bidirectional"))
      (node (ref "IC2") (pin "4") (pinfunction "GND_4") (pintype "bidirectional"))
      (node (ref "IC4") (pin "4") (pinfunction "GND_4") (pintype "bidirectional"))
      (node (ref "JP6") (pin "P$6") (pinfunction "GND_P$6") (pintype "bidirectional"))
      (node (ref "LED1") (pin "2") (pinfunction "C_2") (pintype "passive"))
      (node (ref "LED2") (pin "2") (pinfunction "C_2") (pintype "passive"))
      (node (ref "PB1") (pin "3") (pinfunction "2_3") (pintype "passive"))
      (node (ref "PB1") (pin "4") (pinfunction "2_4") (pintype "passive"))
      (node (ref "PB2") (pin "1") (pinfunction "1_1") (pintype "passive"))
      (node (ref "PB2") (pin "2") (pinfunction "1_2") (pintype "passive"))
      (node (ref "PB3") (pin "1") (pinfunction "1_1") (pintype "passive"))
      (node (ref "PB3") (pin "2") (pinfunction "1_2") (pintype "passive"))
      (node (ref "R1") (pin "1") (pinfunction "1_1") (pintype "passive"))
      (node (ref "R13") (pin "1") (pinfunction "1_1") (pintype "passive"))
      (node (ref "R17") (pin "1") (pinfunction "1_1") (pintype "passive"))
      (node (ref "R5") (pin "1") (pinfunction "1_1") (pintype "passive"))
      (node (ref "R6") (pin "1") (pinfunction "1_1") (pintype "passive"))
      (node (ref "U$1") (pin "2") (pinfunction "GND_2") (pintype "bidirectional"))
      (node (ref "UC1") (pin "22") (pinfunction "GND_22") (pintype "bidirectional"))
      (node (ref "UC1") (pin "8") (pinfunction "GND_8") (pintype "bidirectional"))
    )
    (net (code "38") (name "Net-(C24-Pad1)") (class "Default")
      (node (ref "C24") (pin "1") (pinfunction "1_1") (pintype "passive"))
      (node (ref "R4") (pin "1") (pinfunction "1_1") (pintype "passive"))
    )
    (net (code "39") (name "Net-(CON6-+5V)") (class "Default")
      (node (ref "CON6") (pin "2") (pinfunction "+5V_2") (pintype "passive"))
      (node (ref "F2") (pin "2") (pinfunction "2_2") (pintype "passive"))
    )
    (net (code "40") (name "Net-(CON6-+12V)") (class "Default")
      (node (ref "CON6") (pin "1") (pinfunction "+12V_1") (pintype "passive"))
      (node (ref "F1") (pin "2") (pinfunction "2_2") (pintype "passive"))
    )
    (net (code "41") (name "Net-(IC1-C1+)") (class "Default")
      (node (ref "C12") (pin "1") (pinfunction "1_1") (pintype "passive"))
      (node (ref "IC1") (pin "1") (pinfunction "C1+_1") (pintype "bidirectional"))
    )
    (net (code "42") (name "Net-(IC1-C1-)") (class "Default")
      (node (ref "C12") (pin "2") (pinfunction "2_2") (pintype "passive"))
      (node (ref "IC1") (pin "3") (pinfunction "C1-_3") (pintype "bidirectional"))
    )
    (net (code "43") (name "Net-(IC1-C2+)") (class "Default")
      (node (ref "C13") (pin "1") (pinfunction "1_1") (pintype "passive"))
      (node (ref "IC1") (pin "4") (pinfunction "C2+_4") (pintype "bidirectional"))
    )
    (net (code "44") (name "Net-(IC1-C2-)") (class "Default")
      (node (ref "C13") (pin "2") (pinfunction "2_2") (pintype "passive"))
      (node (ref "IC1") (pin "5") (pinfunction "C2-_5") (pintype "bidirectional"))
    )
    (net (code "45") (name "Net-(IC1-VS+)") (class "Default")
      (node (ref "C14") (pin "1") (pinfunction "1_1") (pintype "passive"))
      (node (ref "IC1") (pin "2") (pinfunction "VS+_2") (pintype "bidirectional"))
    )
    (net (code "46") (name "Net-(IC1-VS-)") (class "Default")
      (node (ref "C16") (pin "2") (pinfunction "2_2") (pintype "passive"))
      (node (ref "IC1") (pin "6") (pinfunction "VS-_6") (pintype "bidirectional"))
    )
    (net (code "47") (name "Net-(IC2-FB)") (class "Default")
      (node (ref "IC2") (pin "6") (pinfunction "TAP_6") (pintype "bidirectional"))
      (node (ref "IC2") (pin "7") (pinfunction "FB_7") (pintype "bidirectional"))
    )
    (net (code "48") (name "Net-(IC4-BS)") (class "Default")
      (node (ref "IC4") (pin "1") (pinfunction "BS_1") (pintype "bidirectional"))
      (node (ref "R4") (pin "2") (pinfunction "2_2") (pintype "passive"))
    )
    (net (code "49") (name "Net-(IC4-FB)") (class "Default")
      (node (ref "IC4") (pin "5") (pinfunction "FB_5") (pintype "bidirectional"))
      (node (ref "R15") (pin "2") (pinfunction "2_2") (pintype "passive"))
      (node (ref "R6") (pin "2") (pinfunction "2_2") (pintype "passive"))
    )
    (net (code "50") (name "Net-(IC4-SS)") (class "Default")
      (node (ref "C23") (pin "1") (pinfunction "1_1") (pintype "passive"))
      (node (ref "IC4") (pin "8") (pinfunction "SS_8") (pintype "bidirectional"))
    )
    (net (code "51") (name "Net-(IC4-SW)") (class "Default")
      (node (ref "C24") (pin "2") (pinfunction "2_2") (pintype "passive"))
      (node (ref "IC4") (pin "3") (pinfunction "SW_3") (pintype "bidirectional"))
      (node (ref "L2") (pin "P$1") (pinfunction "1_P$1") (pintype "passive"))
    )
    (net (code "52") (name "Net-(LED1-A)") (class "Default")
      (node (ref "LED1") (pin "1") (pinfunction "A_1") (pintype "passive"))
      (node (ref "R2") (pin "2") (pinfunction "2_2") (pintype "passive"))
    )
    (net (code "53") (name "Net-(LED2-A)") (class "Default")
      (node (ref "LED2") (pin "1") (pinfunction "A_1") (pintype "passive"))
      (node (ref "R3") (pin "2") (pinfunction "2_2") (pintype "passive"))
    )
    (net (code "54") (name "Net-(MOD1-BLK)") (class "Default")
      (node (ref "MOD1") (pin "5") (pinfunction "GND_5") (pintype "passive"))
      (node (ref "MOD1") (pin "6") (pinfunction "BLK_6") (pintype "passive"))
    )
    (net (code "55") (name "Net-(R15-Pad1)") (class "Default")
      (node (ref "R15") (pin "1") (pinfunction "1_1") (pintype "passive"))
      (node (ref "R16") (pin "2") (pinfunction "2_2") (pintype "passive"))
    )
    (net (code "56") (name "Net-(U$1-OUT)") (class "Default")
      (node (ref "R1") (pin "2") (pinfunction "2_2") (pintype "passive"))
      (node (ref "R12") (pin "1") (pinfunction "1_1") (pintype "passive"))
      (node (ref "U$1") (pin "1") (pinfunction "OUT_1") (pintype "bidirectional"))
      (node (ref "U$1") (pin "3") (pinfunction "RL_3") (pintype "bidirectional"))
    )
    (net (code "57") (name "Net-(UC1-AVCC)") (class "Default")
      (node (ref "C20") (pin "1") (pinfunction "1_1") (pintype "passive"))
      (node (ref "L1") (pin "2") (pinfunction "2_2") (pintype "passive"))
      (node (ref "UC1") (pin "20") (pinfunction "AVCC_20") (pintype "bidirectional"))
    )
    (net (code "58") (name "Net-(UC1-PB6(XTAL1{slash}TOSC1))") (class "Default")
      (node (ref "C2") (pin "1") (pinfunction "1_1") (pintype "passive"))
      (node (ref "UC1") (pin "9") (pinfunction "PB6(XTAL1/TOSC1)_9") (pintype "bidirectional"))
      (node (ref "Y1") (pin "2") (pinfunction "2_2") (pintype "passive"))
    )
    (net (code "59") (name "Net-(UC1-PB7(XTAL2{slash}TOSC2))") (class "Default")
      (node (ref "C3") (pin "1") (pinfunction "1_1") (pintype "passive"))
      (node (ref "UC1") (pin "10") (pinfunction "PB7(XTAL2/TOSC2)_10") (pintype "bidirectional"))
      (node (ref "Y1") (pin "1") (pinfunction "1_1") (pintype "passive"))
    )
    (net (code "60") (name "unconnected-(CON1-SHIELD1-Pad9)") (class "Default")
      (node (ref "CON1") (pin "9") (pinfunction "SHIELD1_9") (pintype "passive"))
    )
    (net (code "61") (name "unconnected-(CON1-SHIELD2-Pad10)") (class "Default")
      (node (ref "CON1") (pin "10") (pinfunction "SHIELD2_10") (pintype "passive"))
    )
    (net (code "62") (name "unconnected-(CON2-Pad7)") (class "Default")
      (node (ref "CON2") (pin "7") (pinfunction "7_7") (pintype "passive"))
    )
    (net (code "63") (name "unconnected-(CON2-Pad8)") (class "Default")
      (node (ref "CON2") (pin "8") (pinfunction "8_8") (pintype "passive"))
    )
    (net (code "64") (name "unconnected-(CON2-SHIELD1-Pad9)") (class "Default")
      (node (ref "CON2") (pin "9") (pinfunction "SHIELD1_9") (pintype "passive"))
    )
    (net (code "65") (name "unconnected-(CON2-SHIELD2-Pad10)") (class "Default")
      (node (ref "CON2") (pin "10") (pinfunction "SHIELD2_10") (pintype "passive"))
    )
    (net (code "66") (name "unconnected-(CON3-Pad1)") (class "Default")
      (node (ref "CON3") (pin "1") (pinfunction "1_1") (pintype "passive"))
    )
    (net (code "67") (name "unconnected-(CON3-Pad2)") (class "Default")
      (node (ref "CON3") (pin "2") (pinfunction "2_2") (pintype "passive"))
    )
    (net (code "68") (name "unconnected-(CON3-Pad7)") (class "Default")
      (node (ref "CON3") (pin "7") (pinfunction "7_7") (pintype "passive"))
    )
    (net (code "69") (name "unconnected-(CON3-Pad8)") (class "Default")
      (node (ref "CON3") (pin "8") (pinfunction "8_8") (pintype "passive"))
    )
    (net (code "70") (name "unconnected-(CON3-SHIELD1-Pad9)") (class "Default")
      (node (ref "CON3") (pin "9") (pinfunction "SHIELD1_9") (pintype "passive"))
    )
    (net (code "71") (name "unconnected-(CON3-SHIELD2-Pad10)") (class "Default")
      (node (ref "CON3") (pin "10") (pinfunction "SHIELD2_10") (pintype "passive"))
    )
    (net (code "72") (name "unconnected-(CON4-SHIELD1-Pad9)") (class "Default")
      (node (ref "CON4") (pin "9") (pinfunction "SHIELD1_9") (pintype "passive"))
    )
    (net (code "73") (name "unconnected-(CON4-SHIELD2-Pad10)") (class "Default")
      (node (ref "CON4") (pin "10") (pinfunction "SHIELD2_10") (pintype "passive"))
    )
    (net (code "74") (name "unconnected-(CON5-SHIELD1-Pad9)") (class "Default")
      (node (ref "CON5") (pin "9") (pinfunction "SHIELD1_9") (pintype "passive"))
    )
    (net (code "75") (name "unconnected-(CON5-SHIELD2-Pad10)") (class "Default")
      (node (ref "CON5") (pin "10") (pinfunction "SHIELD2_10") (pintype "passive"))
    )
    (net (code "76") (name "unconnected-(CON9-Pad1)") (class "Default")
      (node (ref "CON9") (pin "1") (pinfunction "1_1") (pintype "passive"))
    )
    (net (code "77") (name "unconnected-(CON9-Pad2)") (class "Default")
      (node (ref "CON9") (pin "2") (pinfunction "2_2") (pintype "passive"))
    )
    (net (code "78") (name "unconnected-(CON9-Pad3)") (class "Default")
      (node (ref "CON9") (pin "3") (pinfunction "3_3") (pintype "passive"))
    )
    (net (code "79") (name "unconnected-(CON9-Pad4)") (class "Default")
      (node (ref "CON9") (pin "4") (pinfunction "4_4") (pintype "passive"))
    )
    (net (code "80") (name "unconnected-(CON9-Pad5)") (class "Default")
      (node (ref "CON9") (pin "5") (pinfunction "5_5") (pintype "passive"))
    )
    (net (code "81") (name "unconnected-(CON9-Pad6)") (class "Default")
      (node (ref "CON9") (pin "6") (pinfunction "6_6") (pintype "passive"))
    )
    (net (code "82") (name "unconnected-(CON9-Pad7)") (class "Default")
      (node (ref "CON9") (pin "7") (pinfunction "7_7") (pintype "passive"))
    )
    (net (code "83") (name "unconnected-(CON9-Pad8)") (class "Default")
      (node (ref "CON9") (pin "8") (pinfunction "8_8") (pintype "passive"))
    )
    (net (code "84") (name "unconnected-(CON10-Pad1)") (class "Default")
      (node (ref "CON10") (pin "1") (pinfunction "1_1") (pintype "passive"))
    )
    (net (code "85") (name "unconnected-(CON10-Pad2)") (class "Default")
      (node (ref "CON10") (pin "2") (pinfunction "2_2") (pintype "passive"))
    )
    (net (code "86") (name "unconnected-(CON10-Pad3)") (class "Default")
      (node (ref "CON10") (pin "3") (pinfunction "3_3") (pintype "passive"))
    )
    (net (code "87") (name "unconnected-(CON10-Pad4)") (class "Default")
      (node (ref "CON10") (pin "4") (pinfunction "4_4") (pintype "passive"))
    )
    (net (code "88") (name "unconnected-(CON10-Pad5)") (class "Default")
      (node (ref "CON10") (pin "5") (pinfunction "5_5") (pintype "passive"))
    )
    (net (code "89") (name "unconnected-(CON10-Pad6)") (class "Default")
      (node (ref "CON10") (pin "6") (pinfunction "6_6") (pintype "passive"))
    )
    (net (code "90") (name "unconnected-(CON10-Pad7)") (class "Default")
      (node (ref "CON10") (pin "7") (pinfunction "7_7") (pintype "passive"))
    )
    (net (code "91") (name "unconnected-(CON10-Pad8)") (class "Default")
      (node (ref "CON10") (pin "8") (pinfunction "8_8") (pintype "passive"))
    )
    (net (code "92") (name "unconnected-(CON11-Pad1)") (class "Default")
      (node (ref "CON11") (pin "1") (pinfunction "1_1") (pintype "passive"))
    )
    (net (code "93") (name "unconnected-(CON11-Pad2)") (class "Default")
      (node (ref "CON11") (pin "2") (pinfunction "2_2") (pintype "passive"))
    )
    (net (code "94") (name "unconnected-(CON11-Pad3)") (class "Default")
      (node (ref "CON11") (pin "3") (pinfunction "3_3") (pintype "passive"))
    )
    (net (code "95") (name "unconnected-(CON11-Pad4)") (class "Default")
      (node (ref "CON11") (pin "4") (pinfunction "4_4") (pintype "passive"))
    )
    (net (code "96") (name "unconnected-(CON11-Pad5)") (class "Default")
      (node (ref "CON11") (pin "5") (pinfunction "5_5") (pintype "passive"))
    )
    (net (code "97") (name "unconnected-(CON11-Pad6)") (class "Default")
      (node (ref "CON11") (pin "6") (pinfunction "6_6") (pintype "passive"))
    )
    (net (code "98") (name "unconnected-(CON11-Pad7)") (class "Default")
      (node (ref "CON11") (pin "7") (pinfunction "7_7") (pintype "passive"))
    )
    (net (code "99") (name "unconnected-(CON11-Pad8)") (class "Default")
      (node (ref "CON11") (pin "8") (pinfunction "8_8") (pintype "passive"))
    )
    (net (code "100") (name "unconnected-(IC2-ERROR'-Pad5)") (class "Default")
      (node (ref "IC2") (pin "5") (pinfunction "ERROR'_5") (pintype "bidirectional"))
    )
    (net (code "101") (name "unconnected-(IC4-NC-Pad6)") (class "Default")
      (node (ref "IC4") (pin "6") (pinfunction "NC_6") (pintype "bidirectional"))
    )
    (net (code "102") (name "unconnected-(JP6-CTS-PadP$5)") (class "Default")
      (node (ref "JP6") (pin "P$5") (pinfunction "CTS_P$5") (pintype "bidirectional"))
    )
    (net (code "103") (name "unconnected-(JP6-DTR-PadP$1)") (class "Default")
      (node (ref "JP6") (pin "P$1") (pinfunction "DTR_P$1") (pintype "bidirectional"))
    )
    (net (code "104") (name "unconnected-(MOD1-GRN-Pad1)") (class "Default")
      (node (ref "MOD1") (pin "1") (pinfunction "GRN_1") (pintype "passive"))
    )
  )
)
